# LED_Treiber.net
KiCad netlist of a schematic drawn in Altium Designer
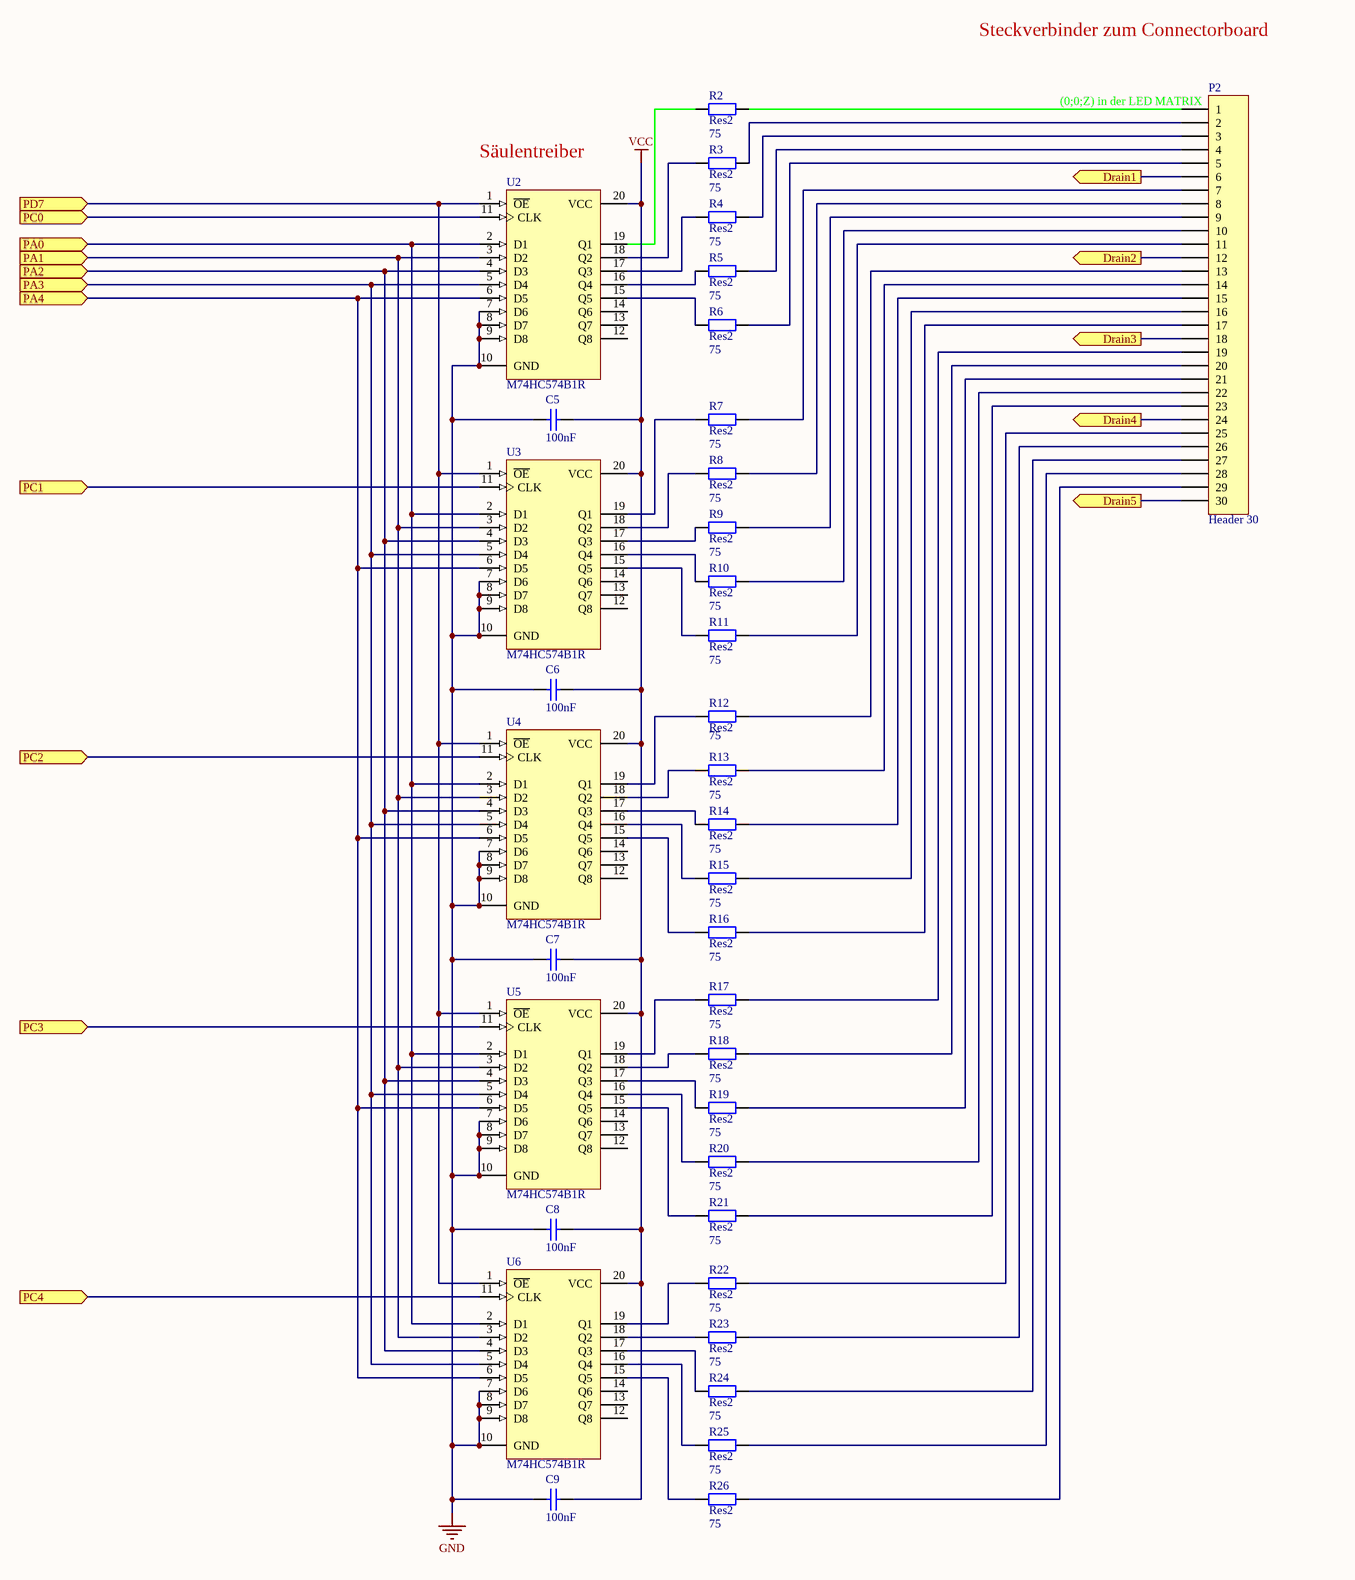
[diagram p0: LED_Treiber.SchDoc]

(export (version "E")
  (design (tool "Eeschema 10.0.6"))
  (components
    (comp (ref "C5")
      (value "100nF")
      (footprint "Miscellaneous Devices:R38")
      (description "Capacitor")
      (fields (field (name "Comment") "Cap") (field (name "PUBLISHER") "Altium Limited"))
      (libsource (lib "Miscellaneous Devices") (part "Cap"))
    )
    (comp (ref "C6")
      (value "100nF")
      (footprint "Miscellaneous Devices:R38")
      (description "Capacitor")
      (fields (field (name "Comment") "Cap") (field (name "PUBLISHER") "Altium Limited"))
      (libsource (lib "Miscellaneous Devices") (part "Cap"))
    )
    (comp (ref "C7")
      (value "100nF")
      (footprint "Miscellaneous Devices:R38")
      (description "Capacitor")
      (fields (field (name "Comment") "Cap") (field (name "PUBLISHER") "Altium Limited"))
      (libsource (lib "Miscellaneous Devices") (part "Cap"))
    )
    (comp (ref "C8")
      (value "100nF")
      (footprint "Miscellaneous Devices:R38")
      (description "Capacitor")
      (fields (field (name "Comment") "Cap") (field (name "PUBLISHER") "Altium Limited"))
      (libsource (lib "Miscellaneous Devices") (part "Cap"))
    )
    (comp (ref "C9")
      (value "100nF")
      (footprint "Miscellaneous Devices:R38")
      (description "Capacitor")
      (fields (field (name "Comment") "Cap") (field (name "PUBLISHER") "Altium Limited"))
      (libsource (lib "Miscellaneous Devices") (part "Cap"))
    )
    (comp (ref "P2")
      (value "Header 30")
      (footprint "HDR1X30")
      (description "Header, 30-Pin")
      (fields (field (name "PUBLISHER") "Altium Limited"))
      (libsource (lib "Miscellaneous Connectors") (part "Header 30"))
    )
    (comp (ref "R2")
      (value "Res2")
      (footprint "Miscellaneous Devices:R38")
      (description "Resistor")
      (fields (field (name "ALTIUM_VALUE") "75") (field (name "PUBLISHER") "Altium Limited"))
      (libsource (lib "Miscellaneous Devices") (part "Res2"))
    )
    (comp (ref "R3")
      (value "Res2")
      (footprint "Miscellaneous Devices:R38")
      (description "Resistor")
      (fields (field (name "ALTIUM_VALUE") "75") (field (name "PUBLISHER") "Altium Limited"))
      (libsource (lib "Miscellaneous Devices") (part "Res2"))
    )
    (comp (ref "R4")
      (value "Res2")
      (footprint "Miscellaneous Devices:R38")
      (description "Resistor")
      (fields (field (name "ALTIUM_VALUE") "75") (field (name "PUBLISHER") "Altium Limited"))
      (libsource (lib "Miscellaneous Devices") (part "Res2"))
    )
    (comp (ref "R5")
      (value "Res2")
      (footprint "Miscellaneous Devices:R38")
      (description "Resistor")
      (fields (field (name "ALTIUM_VALUE") "75") (field (name "PUBLISHER") "Altium Limited"))
      (libsource (lib "Miscellaneous Devices") (part "Res2"))
    )
    (comp (ref "R6")
      (value "Res2")
      (footprint "Miscellaneous Devices:R38")
      (description "Resistor")
      (fields (field (name "ALTIUM_VALUE") "75") (field (name "PUBLISHER") "Altium Limited"))
      (libsource (lib "Miscellaneous Devices") (part "Res2"))
    )
    (comp (ref "R7")
      (value "Res2")
      (footprint "Miscellaneous Devices:R38")
      (description "Resistor")
      (fields (field (name "ALTIUM_VALUE") "75") (field (name "PUBLISHER") "Altium Limited"))
      (libsource (lib "Miscellaneous Devices") (part "Res2"))
    )
    (comp (ref "R8")
      (value "Res2")
      (footprint "Miscellaneous Devices:R38")
      (description "Resistor")
      (fields (field (name "ALTIUM_VALUE") "75") (field (name "PUBLISHER") "Altium Limited"))
      (libsource (lib "Miscellaneous Devices") (part "Res2"))
    )
    (comp (ref "R9")
      (value "Res2")
      (footprint "Miscellaneous Devices:R38")
      (description "Resistor")
      (fields (field (name "ALTIUM_VALUE") "75") (field (name "PUBLISHER") "Altium Limited"))
      (libsource (lib "Miscellaneous Devices") (part "Res2"))
    )
    (comp (ref "R10")
      (value "Res2")
      (footprint "Miscellaneous Devices:R38")
      (description "Resistor")
      (fields (field (name "ALTIUM_VALUE") "75") (field (name "PUBLISHER") "Altium Limited"))
      (libsource (lib "Miscellaneous Devices") (part "Res2"))
    )
    (comp (ref "R11")
      (value "Res2")
      (footprint "Miscellaneous Devices:R38")
      (description "Resistor")
      (fields (field (name "ALTIUM_VALUE") "75") (field (name "PUBLISHER") "Altium Limited"))
      (libsource (lib "Miscellaneous Devices") (part "Res2"))
    )
    (comp (ref "R12")
      (value "Res2")
      (footprint "Miscellaneous Devices:R38")
      (description "Resistor")
      (fields (field (name "ALTIUM_VALUE") "75") (field (name "PUBLISHER") "Altium Limited"))
      (libsource (lib "Miscellaneous Devices") (part "Res2"))
    )
    (comp (ref "R13")
      (value "Res2")
      (footprint "Miscellaneous Devices:R38")
      (description "Resistor")
      (fields (field (name "ALTIUM_VALUE") "75") (field (name "PUBLISHER") "Altium Limited"))
      (libsource (lib "Miscellaneous Devices") (part "Res2"))
    )
    (comp (ref "R14")
      (value "Res2")
      (footprint "Miscellaneous Devices:R38")
      (description "Resistor")
      (fields (field (name "ALTIUM_VALUE") "75") (field (name "PUBLISHER") "Altium Limited"))
      (libsource (lib "Miscellaneous Devices") (part "Res2"))
    )
    (comp (ref "R15")
      (value "Res2")
      (footprint "Miscellaneous Devices:R38")
      (description "Resistor")
      (fields (field (name "ALTIUM_VALUE") "75") (field (name "PUBLISHER") "Altium Limited"))
      (libsource (lib "Miscellaneous Devices") (part "Res2"))
    )
    (comp (ref "R16")
      (value "Res2")
      (footprint "Miscellaneous Devices:R38")
      (description "Resistor")
      (fields (field (name "ALTIUM_VALUE") "75") (field (name "PUBLISHER") "Altium Limited"))
      (libsource (lib "Miscellaneous Devices") (part "Res2"))
    )
    (comp (ref "R17")
      (value "Res2")
      (footprint "Miscellaneous Devices:R38")
      (description "Resistor")
      (fields (field (name "ALTIUM_VALUE") "75") (field (name "PUBLISHER") "Altium Limited"))
      (libsource (lib "Miscellaneous Devices") (part "Res2"))
    )
    (comp (ref "R18")
      (value "Res2")
      (footprint "Miscellaneous Devices:R38")
      (description "Resistor")
      (fields (field (name "ALTIUM_VALUE") "75") (field (name "PUBLISHER") "Altium Limited"))
      (libsource (lib "Miscellaneous Devices") (part "Res2"))
    )
    (comp (ref "R19")
      (value "Res2")
      (footprint "Miscellaneous Devices:R38")
      (description "Resistor")
      (fields (field (name "ALTIUM_VALUE") "75") (field (name "PUBLISHER") "Altium Limited"))
      (libsource (lib "Miscellaneous Devices") (part "Res2"))
    )
    (comp (ref "R20")
      (value "Res2")
      (footprint "Miscellaneous Devices:R38")
      (description "Resistor")
      (fields (field (name "ALTIUM_VALUE") "75") (field (name "PUBLISHER") "Altium Limited"))
      (libsource (lib "Miscellaneous Devices") (part "Res2"))
    )
    (comp (ref "R21")
      (value "Res2")
      (footprint "Miscellaneous Devices:R38")
      (description "Resistor")
      (fields (field (name "ALTIUM_VALUE") "75") (field (name "PUBLISHER") "Altium Limited"))
      (libsource (lib "Miscellaneous Devices") (part "Res2"))
    )
    (comp (ref "R22")
      (value "Res2")
      (footprint "Miscellaneous Devices:R38")
      (description "Resistor")
      (fields (field (name "ALTIUM_VALUE") "75") (field (name "PUBLISHER") "Altium Limited"))
      (libsource (lib "Miscellaneous Devices") (part "Res2"))
    )
    (comp (ref "R23")
      (value "Res2")
      (footprint "Miscellaneous Devices:R38")
      (description "Resistor")
      (fields (field (name "ALTIUM_VALUE") "75") (field (name "PUBLISHER") "Altium Limited"))
      (libsource (lib "Miscellaneous Devices") (part "Res2"))
    )
    (comp (ref "R24")
      (value "Res2")
      (footprint "Miscellaneous Devices:R38")
      (description "Resistor")
      (fields (field (name "ALTIUM_VALUE") "75") (field (name "PUBLISHER") "Altium Limited"))
      (libsource (lib "Miscellaneous Devices") (part "Res2"))
    )
    (comp (ref "R25")
      (value "Res2")
      (footprint "Miscellaneous Devices:R38")
      (description "Resistor")
      (fields (field (name "ALTIUM_VALUE") "75") (field (name "PUBLISHER") "Altium Limited"))
      (libsource (lib "Miscellaneous Devices") (part "Res2"))
    )
    (comp (ref "R26")
      (value "Res2")
      (footprint "Miscellaneous Devices:R38")
      (description "Resistor")
      (fields (field (name "ALTIUM_VALUE") "75") (field (name "PUBLISHER") "Altium Limited"))
      (libsource (lib "Miscellaneous Devices") (part "Res2"))
    )
    (comp (ref "U2")
      (value "M74HC574B1R")
      (footprint "DIP20")
      (description "Octal D-Type Flip-Flop with 3-State Output Non-Inverting")
      (fields (field (name "PUBLISHER") "Altium Limited"))
      (libsource (lib "ST Logic Flip-Flop") (part "M74HC574B1R"))
    )
    (comp (ref "U3")
      (value "M74HC574B1R")
      (footprint "DIP20")
      (description "Octal D-Type Flip-Flop with 3-State Output Non-Inverting")
      (fields (field (name "PUBLISHER") "Altium Limited"))
      (libsource (lib "ST Logic Flip-Flop") (part "M74HC574B1R"))
    )
    (comp (ref "U4")
      (value "M74HC574B1R")
      (footprint "DIP20")
      (description "Octal D-Type Flip-Flop with 3-State Output Non-Inverting")
      (fields (field (name "PUBLISHER") "Altium Limited"))
      (libsource (lib "ST Logic Flip-Flop") (part "M74HC574B1R"))
    )
    (comp (ref "U5")
      (value "M74HC574B1R")
      (footprint "DIP20")
      (description "Octal D-Type Flip-Flop with 3-State Output Non-Inverting")
      (fields (field (name "PUBLISHER") "Altium Limited"))
      (libsource (lib "ST Logic Flip-Flop") (part "M74HC574B1R"))
    )
    (comp (ref "U6")
      (value "M74HC574B1R")
      (footprint "DIP20")
      (description "Octal D-Type Flip-Flop with 3-State Output Non-Inverting")
      (fields (field (name "PUBLISHER") "Altium Limited"))
      (libsource (lib "ST Logic Flip-Flop") (part "M74HC574B1R"))
    )
  )
  (nets
    (net (code "1") (name "/Drain1") (class "Default")
      (node (ref "P2") (pin "6") (pinfunction "6_6") (pintype "passive"))
    )
    (net (code "2") (name "/Drain2") (class "Default")
      (node (ref "P2") (pin "12") (pinfunction "12_12") (pintype "passive"))
    )
    (net (code "3") (name "/Drain3") (class "Default")
      (node (ref "P2") (pin "18") (pinfunction "18_18") (pintype "passive"))
    )
    (net (code "4") (name "/Drain4") (class "Default")
      (node (ref "P2") (pin "24") (pinfunction "24_24") (pintype "passive"))
    )
    (net (code "5") (name "/Drain5") (class "Default")
      (node (ref "P2") (pin "30") (pinfunction "30_30") (pintype "passive"))
    )
    (net (code "6") (name "/PA0") (class "Default")
      (node (ref "U2") (pin "2") (pinfunction "D1_2") (pintype "input"))
      (node (ref "U3") (pin "2") (pinfunction "D1_2") (pintype "input"))
      (node (ref "U4") (pin "2") (pinfunction "D1_2") (pintype "input"))
      (node (ref "U5") (pin "2") (pinfunction "D1_2") (pintype "input"))
      (node (ref "U6") (pin "2") (pinfunction "D1_2") (pintype "input"))
    )
    (net (code "7") (name "/PA1") (class "Default")
      (node (ref "U2") (pin "3") (pinfunction "D2_3") (pintype "input"))
      (node (ref "U3") (pin "3") (pinfunction "D2_3") (pintype "input"))
      (node (ref "U4") (pin "3") (pinfunction "D2_3") (pintype "input"))
      (node (ref "U5") (pin "3") (pinfunction "D2_3") (pintype "input"))
      (node (ref "U6") (pin "3") (pinfunction "D2_3") (pintype "input"))
    )
    (net (code "8") (name "/PA2") (class "Default")
      (node (ref "U2") (pin "4") (pinfunction "D3_4") (pintype "input"))
      (node (ref "U3") (pin "4") (pinfunction "D3_4") (pintype "input"))
      (node (ref "U4") (pin "4") (pinfunction "D3_4") (pintype "input"))
      (node (ref "U5") (pin "4") (pinfunction "D3_4") (pintype "input"))
      (node (ref "U6") (pin "4") (pinfunction "D3_4") (pintype "input"))
    )
    (net (code "9") (name "/PA3") (class "Default")
      (node (ref "U2") (pin "5") (pinfunction "D4_5") (pintype "input"))
      (node (ref "U3") (pin "5") (pinfunction "D4_5") (pintype "input"))
      (node (ref "U4") (pin "5") (pinfunction "D4_5") (pintype "input"))
      (node (ref "U5") (pin "5") (pinfunction "D4_5") (pintype "input"))
      (node (ref "U6") (pin "5") (pinfunction "D4_5") (pintype "input"))
    )
    (net (code "10") (name "/PA4") (class "Default")
      (node (ref "U2") (pin "6") (pinfunction "D5_6") (pintype "input"))
      (node (ref "U3") (pin "6") (pinfunction "D5_6") (pintype "input"))
      (node (ref "U4") (pin "6") (pinfunction "D5_6") (pintype "input"))
      (node (ref "U5") (pin "6") (pinfunction "D5_6") (pintype "input"))
      (node (ref "U6") (pin "6") (pinfunction "D5_6") (pintype "input"))
    )
    (net (code "11") (name "/PC0") (class "Default")
      (node (ref "U2") (pin "11") (pinfunction "CLK_11") (pintype "input"))
    )
    (net (code "12") (name "/PC1") (class "Default")
      (node (ref "U3") (pin "11") (pinfunction "CLK_11") (pintype "input"))
    )
    (net (code "13") (name "/PC2") (class "Default")
      (node (ref "U4") (pin "11") (pinfunction "CLK_11") (pintype "input"))
    )
    (net (code "14") (name "/PC3") (class "Default")
      (node (ref "U5") (pin "11") (pinfunction "CLK_11") (pintype "input"))
    )
    (net (code "15") (name "/PC4") (class "Default")
      (node (ref "U6") (pin "11") (pinfunction "CLK_11") (pintype "input"))
    )
    (net (code "16") (name "/PD7") (class "Default")
      (node (ref "U2") (pin "1") (pinfunction "~{OE}_1") (pintype "input"))
      (node (ref "U3") (pin "1") (pinfunction "~{OE}_1") (pintype "input"))
      (node (ref "U4") (pin "1") (pinfunction "~{OE}_1") (pintype "input"))
      (node (ref "U5") (pin "1") (pinfunction "~{OE}_1") (pintype "input"))
      (node (ref "U6") (pin "1") (pinfunction "~{OE}_1") (pintype "input"))
    )
    (net (code "17") (name "GND") (class "Default")
      (node (ref "C5") (pin "1") (pinfunction "1_1") (pintype "passive"))
      (node (ref "C6") (pin "1") (pinfunction "1_1") (pintype "passive"))
      (node (ref "C7") (pin "1") (pinfunction "1_1") (pintype "passive"))
      (node (ref "C8") (pin "1") (pinfunction "1_1") (pintype "passive"))
      (node (ref "C9") (pin "1") (pinfunction "1_1") (pintype "passive"))
      (node (ref "U2") (pin "10") (pinfunction "GND_10") (pintype "power_in"))
      (node (ref "U2") (pin "7") (pinfunction "D6_7") (pintype "input"))
      (node (ref "U2") (pin "8") (pinfunction "D7_8") (pintype "input"))
      (node (ref "U2") (pin "9") (pinfunction "D8_9") (pintype "input"))
      (node (ref "U3") (pin "10") (pinfunction "GND_10") (pintype "power_in"))
      (node (ref "U3") (pin "7") (pinfunction "D6_7") (pintype "input"))
      (node (ref "U3") (pin "8") (pinfunction "D7_8") (pintype "input"))
      (node (ref "U3") (pin "9") (pinfunction "D8_9") (pintype "input"))
      (node (ref "U4") (pin "10") (pinfunction "GND_10") (pintype "power_in"))
      (node (ref "U4") (pin "7") (pinfunction "D6_7") (pintype "input"))
      (node (ref "U4") (pin "8") (pinfunction "D7_8") (pintype "input"))
      (node (ref "U4") (pin "9") (pinfunction "D8_9") (pintype "input"))
      (node (ref "U5") (pin "10") (pinfunction "GND_10") (pintype "power_in"))
      (node (ref "U5") (pin "7") (pinfunction "D6_7") (pintype "input"))
      (node (ref "U5") (pin "8") (pinfunction "D7_8") (pintype "input"))
      (node (ref "U5") (pin "9") (pinfunction "D8_9") (pintype "input"))
      (node (ref "U6") (pin "10") (pinfunction "GND_10") (pintype "power_in"))
      (node (ref "U6") (pin "7") (pinfunction "D6_7") (pintype "input"))
      (node (ref "U6") (pin "8") (pinfunction "D7_8") (pintype "input"))
      (node (ref "U6") (pin "9") (pinfunction "D8_9") (pintype "input"))
    )
    (net (code "18") (name "Net-(P2-Pad1)") (class "Default")
      (node (ref "P2") (pin "1") (pinfunction "1_1") (pintype "passive"))
      (node (ref "R2") (pin "2") (pinfunction "2_2") (pintype "passive"))
    )
    (net (code "19") (name "Net-(P2-Pad2)") (class "Default")
      (node (ref "P2") (pin "2") (pinfunction "2_2") (pintype "passive"))
      (node (ref "R3") (pin "2") (pinfunction "2_2") (pintype "passive"))
    )
    (net (code "20") (name "Net-(P2-Pad3)") (class "Default")
      (node (ref "P2") (pin "3") (pinfunction "3_3") (pintype "passive"))
      (node (ref "R4") (pin "2") (pinfunction "2_2") (pintype "passive"))
    )
    (net (code "21") (name "Net-(P2-Pad4)") (class "Default")
      (node (ref "P2") (pin "4") (pinfunction "4_4") (pintype "passive"))
      (node (ref "R5") (pin "2") (pinfunction "2_2") (pintype "passive"))
    )
    (net (code "22") (name "Net-(P2-Pad5)") (class "Default")
      (node (ref "P2") (pin "5") (pinfunction "5_5") (pintype "passive"))
      (node (ref "R6") (pin "2") (pinfunction "2_2") (pintype "passive"))
    )
    (net (code "23") (name "Net-(P2-Pad7)") (class "Default")
      (node (ref "P2") (pin "7") (pinfunction "7_7") (pintype "passive"))
      (node (ref "R7") (pin "2") (pinfunction "2_2") (pintype "passive"))
    )
    (net (code "24") (name "Net-(P2-Pad8)") (class "Default")
      (node (ref "P2") (pin "8") (pinfunction "8_8") (pintype "passive"))
      (node (ref "R8") (pin "2") (pinfunction "2_2") (pintype "passive"))
    )
    (net (code "25") (name "Net-(P2-Pad9)") (class "Default")
      (node (ref "P2") (pin "9") (pinfunction "9_9") (pintype "passive"))
      (node (ref "R9") (pin "2") (pinfunction "2_2") (pintype "passive"))
    )
    (net (code "26") (name "Net-(P2-Pad10)") (class "Default")
      (node (ref "P2") (pin "10") (pinfunction "10_10") (pintype "passive"))
      (node (ref "R10") (pin "2") (pinfunction "2_2") (pintype "passive"))
    )
    (net (code "27") (name "Net-(P2-Pad11)") (class "Default")
      (node (ref "P2") (pin "11") (pinfunction "11_11") (pintype "passive"))
      (node (ref "R11") (pin "2") (pinfunction "2_2") (pintype "passive"))
    )
    (net (code "28") (name "Net-(P2-Pad13)") (class "Default")
      (node (ref "P2") (pin "13") (pinfunction "13_13") (pintype "passive"))
      (node (ref "R12") (pin "2") (pinfunction "2_2") (pintype "passive"))
    )
    (net (code "29") (name "Net-(P2-Pad14)") (class "Default")
      (node (ref "P2") (pin "14") (pinfunction "14_14") (pintype "passive"))
      (node (ref "R13") (pin "2") (pinfunction "2_2") (pintype "passive"))
    )
    (net (code "30") (name "Net-(P2-Pad15)") (class "Default")
      (node (ref "P2") (pin "15") (pinfunction "15_15") (pintype "passive"))
      (node (ref "R14") (pin "2") (pinfunction "2_2") (pintype "passive"))
    )
    (net (code "31") (name "Net-(P2-Pad16)") (class "Default")
      (node (ref "P2") (pin "16") (pinfunction "16_16") (pintype "passive"))
      (node (ref "R15") (pin "2") (pinfunction "2_2") (pintype "passive"))
    )
    (net (code "32") (name "Net-(P2-Pad17)") (class "Default")
      (node (ref "P2") (pin "17") (pinfunction "17_17") (pintype "passive"))
      (node (ref "R16") (pin "2") (pinfunction "2_2") (pintype "passive"))
    )
    (net (code "33") (name "Net-(P2-Pad19)") (class "Default")
      (node (ref "P2") (pin "19") (pinfunction "19_19") (pintype "passive"))
      (node (ref "R17") (pin "2") (pinfunction "2_2") (pintype "passive"))
    )
    (net (code "34") (name "Net-(P2-Pad20)") (class "Default")
      (node (ref "P2") (pin "20") (pinfunction "20_20") (pintype "passive"))
      (node (ref "R18") (pin "2") (pinfunction "2_2") (pintype "passive"))
    )
    (net (code "35") (name "Net-(P2-Pad21)") (class "Default")
      (node (ref "P2") (pin "21") (pinfunction "21_21") (pintype "passive"))
      (node (ref "R19") (pin "2") (pinfunction "2_2") (pintype "passive"))
    )
    (net (code "36") (name "Net-(P2-Pad22)") (class "Default")
      (node (ref "P2") (pin "22") (pinfunction "22_22") (pintype "passive"))
      (node (ref "R20") (pin "2") (pinfunction "2_2") (pintype "passive"))
    )
    (net (code "37") (name "Net-(P2-Pad23)") (class "Default")
      (node (ref "P2") (pin "23") (pinfunction "23_23") (pintype "passive"))
      (node (ref "R21") (pin "2") (pinfunction "2_2") (pintype "passive"))
    )
    (net (code "38") (name "Net-(P2-Pad25)") (class "Default")
      (node (ref "P2") (pin "25") (pinfunction "25_25") (pintype "passive"))
      (node (ref "R22") (pin "2") (pinfunction "2_2") (pintype "passive"))
    )
    (net (code "39") (name "Net-(P2-Pad26)") (class "Default")
      (node (ref "P2") (pin "26") (pinfunction "26_26") (pintype "passive"))
      (node (ref "R23") (pin "2") (pinfunction "2_2") (pintype "passive"))
    )
    (net (code "40") (name "Net-(P2-Pad27)") (class "Default")
      (node (ref "P2") (pin "27") (pinfunction "27_27") (pintype "passive"))
      (node (ref "R24") (pin "2") (pinfunction "2_2") (pintype "passive"))
    )
    (net (code "41") (name "Net-(P2-Pad28)") (class "Default")
      (node (ref "P2") (pin "28") (pinfunction "28_28") (pintype "passive"))
      (node (ref "R25") (pin "2") (pinfunction "2_2") (pintype "passive"))
    )
    (net (code "42") (name "Net-(P2-Pad29)") (class "Default")
      (node (ref "P2") (pin "29") (pinfunction "29_29") (pintype "passive"))
      (node (ref "R26") (pin "2") (pinfunction "2_2") (pintype "passive"))
    )
    (net (code "43") (name "Net-(U2-Q1)") (class "Default")
      (node (ref "R2") (pin "1") (pinfunction "1_1") (pintype "passive"))
      (node (ref "U2") (pin "19") (pinfunction "Q1_19") (pintype "tri_state"))
    )
    (net (code "44") (name "Net-(U2-Q2)") (class "Default")
      (node (ref "R3") (pin "1") (pinfunction "1_1") (pintype "passive"))
      (node (ref "U2") (pin "18") (pinfunction "Q2_18") (pintype "tri_state"))
    )
    (net (code "45") (name "Net-(U2-Q3)") (class "Default")
      (node (ref "R4") (pin "1") (pinfunction "1_1") (pintype "passive"))
      (node (ref "U2") (pin "17") (pinfunction "Q3_17") (pintype "tri_state"))
    )
    (net (code "46") (name "Net-(U2-Q4)") (class "Default")
      (node (ref "R5") (pin "1") (pinfunction "1_1") (pintype "passive"))
      (node (ref "U2") (pin "16") (pinfunction "Q4_16") (pintype "tri_state"))
    )
    (net (code "47") (name "Net-(U2-Q5)") (class "Default")
      (node (ref "R6") (pin "1") (pinfunction "1_1") (pintype "passive"))
      (node (ref "U2") (pin "15") (pinfunction "Q5_15") (pintype "tri_state"))
    )
    (net (code "48") (name "Net-(U3-Q1)") (class "Default")
      (node (ref "R7") (pin "1") (pinfunction "1_1") (pintype "passive"))
      (node (ref "U3") (pin "19") (pinfunction "Q1_19") (pintype "tri_state"))
    )
    (net (code "49") (name "Net-(U3-Q2)") (class "Default")
      (node (ref "R8") (pin "1") (pinfunction "1_1") (pintype "passive"))
      (node (ref "U3") (pin "18") (pinfunction "Q2_18") (pintype "tri_state"))
    )
    (net (code "50") (name "Net-(U3-Q3)") (class "Default")
      (node (ref "R9") (pin "1") (pinfunction "1_1") (pintype "passive"))
      (node (ref "U3") (pin "17") (pinfunction "Q3_17") (pintype "tri_state"))
    )
    (net (code "51") (name "Net-(U3-Q4)") (class "Default")
      (node (ref "R10") (pin "1") (pinfunction "1_1") (pintype "passive"))
      (node (ref "U3") (pin "16") (pinfunction "Q4_16") (pintype "tri_state"))
    )
    (net (code "52") (name "Net-(U3-Q5)") (class "Default")
      (node (ref "R11") (pin "1") (pinfunction "1_1") (pintype "passive"))
      (node (ref "U3") (pin "15") (pinfunction "Q5_15") (pintype "tri_state"))
    )
    (net (code "53") (name "Net-(U4-Q1)") (class "Default")
      (node (ref "R12") (pin "1") (pinfunction "1_1") (pintype "passive"))
      (node (ref "U4") (pin "19") (pinfunction "Q1_19") (pintype "tri_state"))
    )
    (net (code "54") (name "Net-(U4-Q2)") (class "Default")
      (node (ref "R13") (pin "1") (pinfunction "1_1") (pintype "passive"))
      (node (ref "U4") (pin "18") (pinfunction "Q2_18") (pintype "tri_state"))
    )
    (net (code "55") (name "Net-(U4-Q3)") (class "Default")
      (node (ref "R14") (pin "1") (pinfunction "1_1") (pintype "passive"))
      (node (ref "U4") (pin "17") (pinfunction "Q3_17") (pintype "tri_state"))
    )
    (net (code "56") (name "Net-(U4-Q4)") (class "Default")
      (node (ref "R15") (pin "1") (pinfunction "1_1") (pintype "passive"))
      (node (ref "U4") (pin "16") (pinfunction "Q4_16") (pintype "tri_state"))
    )
    (net (code "57") (name "Net-(U4-Q5)") (class "Default")
      (node (ref "R16") (pin "1") (pinfunction "1_1") (pintype "passive"))
      (node (ref "U4") (pin "15") (pinfunction "Q5_15") (pintype "tri_state"))
    )
    (net (code "58") (name "Net-(U5-Q1)") (class "Default")
      (node (ref "R17") (pin "1") (pinfunction "1_1") (pintype "passive"))
      (node (ref "U5") (pin "19") (pinfunction "Q1_19") (pintype "tri_state"))
    )
    (net (code "59") (name "Net-(U5-Q2)") (class "Default")
      (node (ref "R18") (pin "1") (pinfunction "1_1") (pintype "passive"))
      (node (ref "U5") (pin "18") (pinfunction "Q2_18") (pintype "tri_state"))
    )
    (net (code "60") (name "Net-(U5-Q3)") (class "Default")
      (node (ref "R19") (pin "1") (pinfunction "1_1") (pintype "passive"))
      (node (ref "U5") (pin "17") (pinfunction "Q3_17") (pintype "tri_state"))
    )
    (net (code "61") (name "Net-(U5-Q4)") (class "Default")
      (node (ref "R20") (pin "1") (pinfunction "1_1") (pintype "passive"))
      (node (ref "U5") (pin "16") (pinfunction "Q4_16") (pintype "tri_state"))
    )
    (net (code "62") (name "Net-(U5-Q5)") (class "Default")
      (node (ref "R21") (pin "1") (pinfunction "1_1") (pintype "passive"))
      (node (ref "U5") (pin "15") (pinfunction "Q5_15") (pintype "tri_state"))
    )
    (net (code "63") (name "Net-(U6-Q1)") (class "Default")
      (node (ref "R22") (pin "1") (pinfunction "1_1") (pintype "passive"))
      (node (ref "U6") (pin "19") (pinfunction "Q1_19") (pintype "tri_state"))
    )
    (net (code "64") (name "Net-(U6-Q2)") (class "Default")
      (node (ref "R23") (pin "1") (pinfunction "1_1") (pintype "passive"))
      (node (ref "U6") (pin "18") (pinfunction "Q2_18") (pintype "tri_state"))
    )
    (net (code "65") (name "Net-(U6-Q3)") (class "Default")
      (node (ref "R24") (pin "1") (pinfunction "1_1") (pintype "passive"))
      (node (ref "U6") (pin "17") (pinfunction "Q3_17") (pintype "tri_state"))
    )
    (net (code "66") (name "Net-(U6-Q4)") (class "Default")
      (node (ref "R25") (pin "1") (pinfunction "1_1") (pintype "passive"))
      (node (ref "U6") (pin "16") (pinfunction "Q4_16") (pintype "tri_state"))
    )
    (net (code "67") (name "Net-(U6-Q5)") (class "Default")
      (node (ref "R26") (pin "1") (pinfunction "1_1") (pintype "passive"))
      (node (ref "U6") (pin "15") (pinfunction "Q5_15") (pintype "tri_state"))
    )
    (net (code "68") (name "VCC") (class "Default")
      (node (ref "C5") (pin "2") (pinfunction "2_2") (pintype "passive"))
      (node (ref "C6") (pin "2") (pinfunction "2_2") (pintype "passive"))
      (node (ref "C7") (pin "2") (pinfunction "2_2") (pintype "passive"))
      (node (ref "C8") (pin "2") (pinfunction "2_2") (pintype "passive"))
      (node (ref "C9") (pin "2") (pinfunction "2_2") (pintype "passive"))
      (node (ref "U2") (pin "20") (pinfunction "VCC_20") (pintype "power_in"))
      (node (ref "U3") (pin "20") (pinfunction "VCC_20") (pintype "power_in"))
      (node (ref "U4") (pin "20") (pinfunction "VCC_20") (pintype "power_in"))
      (node (ref "U5") (pin "20") (pinfunction "VCC_20") (pintype "power_in"))
      (node (ref "U6") (pin "20") (pinfunction "VCC_20") (pintype "power_in"))
    )
    (net (code "69") (name "unconnected-(U2-Q6-Pad14)") (class "Default")
      (node (ref "U2") (pin "14") (pinfunction "Q6_14") (pintype "tri_state"))
    )
    (net (code "70") (name "unconnected-(U2-Q7-Pad13)") (class "Default")
      (node (ref "U2") (pin "13") (pinfunction "Q7_13") (pintype "tri_state"))
    )
    (net (code "71") (name "unconnected-(U2-Q8-Pad12)") (class "Default")
      (node (ref "U2") (pin "12") (pinfunction "Q8_12") (pintype "tri_state"))
    )
    (net (code "72") (name "unconnected-(U3-Q6-Pad14)") (class "Default")
      (node (ref "U3") (pin "14") (pinfunction "Q6_14") (pintype "tri_state"))
    )
    (net (code "73") (name "unconnected-(U3-Q7-Pad13)") (class "Default")
      (node (ref "U3") (pin "13") (pinfunction "Q7_13") (pintype "tri_state"))
    )
    (net (code "74") (name "unconnected-(U3-Q8-Pad12)") (class "Default")
      (node (ref "U3") (pin "12") (pinfunction "Q8_12") (pintype "tri_state"))
    )
    (net (code "75") (name "unconnected-(U4-Q6-Pad14)") (class "Default")
      (node (ref "U4") (pin "14") (pinfunction "Q6_14") (pintype "tri_state"))
    )
    (net (code "76") (name "unconnected-(U4-Q7-Pad13)") (class "Default")
      (node (ref "U4") (pin "13") (pinfunction "Q7_13") (pintype "tri_state"))
    )
    (net (code "77") (name "unconnected-(U4-Q8-Pad12)") (class "Default")
      (node (ref "U4") (pin "12") (pinfunction "Q8_12") (pintype "tri_state"))
    )
    (net (code "78") (name "unconnected-(U5-Q6-Pad14)") (class "Default")
      (node (ref "U5") (pin "14") (pinfunction "Q6_14") (pintype "tri_state"))
    )
    (net (code "79") (name "unconnected-(U5-Q7-Pad13)") (class "Default")
      (node (ref "U5") (pin "13") (pinfunction "Q7_13") (pintype "tri_state"))
    )
    (net (code "80") (name "unconnected-(U5-Q8-Pad12)") (class "Default")
      (node (ref "U5") (pin "12") (pinfunction "Q8_12") (pintype "tri_state"))
    )
    (net (code "81") (name "unconnected-(U6-Q6-Pad14)") (class "Default")
      (node (ref "U6") (pin "14") (pinfunction "Q6_14") (pintype "tri_state"))
    )
    (net (code "82") (name "unconnected-(U6-Q7-Pad13)") (class "Default")
      (node (ref "U6") (pin "13") (pinfunction "Q7_13") (pintype "tri_state"))
    )
    (net (code "83") (name "unconnected-(U6-Q8-Pad12)") (class "Default")
      (node (ref "U6") (pin "12") (pinfunction "Q8_12") (pintype "tri_state"))
    )
  )
)
